# Nucleo.net
KiCad netlist of a schematic drawn in Altium Designer
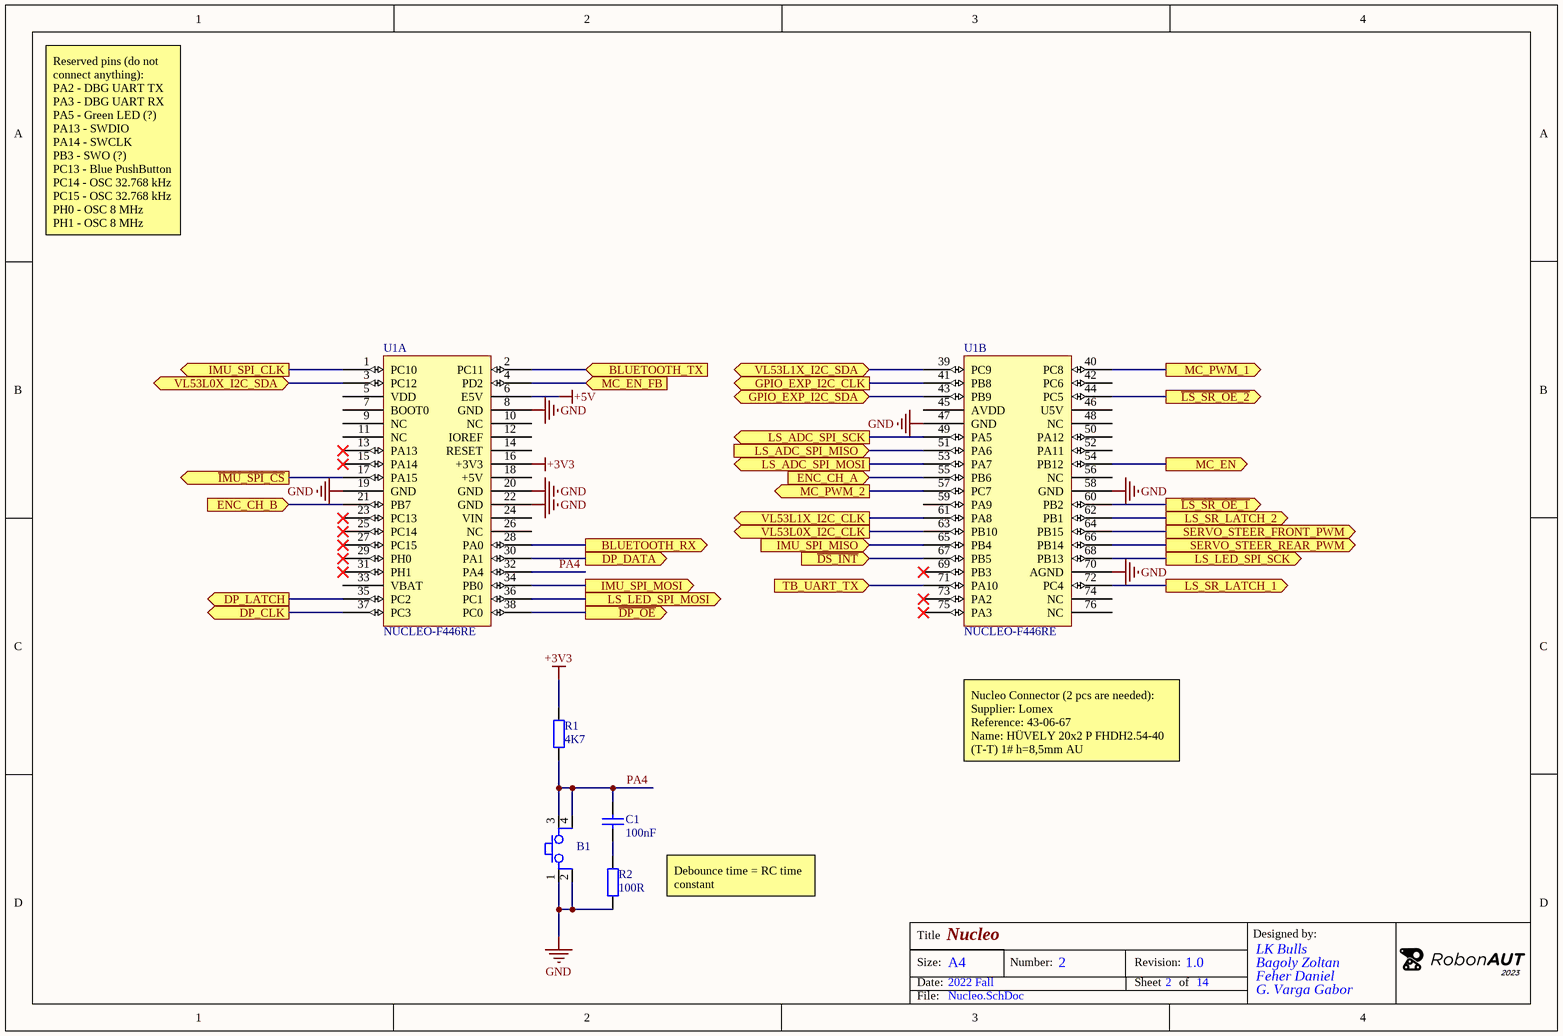
[diagram p0: Nucleo.SchDoc]

(export (version "E")
  (design (tool "Eeschema 10.0.6"))
  (components
    (comp (ref "B1")
      (value "Button")
      (footprint "FP_BTN_SMD")
      (description "Push button")
      (libsource (lib "LKBulls2023") (part "Button 4P"))
    )
    (comp (ref "C1")
      (value "100nF")
      (footprint "FP_0805_CAP_085")
      (description "Capacitor")
      (fields (field (name "TOLERANCE") "10%") (field (name "VOLTAGE") "50V"))
      (libsource (lib "LKBulls2023") (part "CAP"))
    )
    (comp (ref "R1")
      (value "4K7")
      (footprint "FP_0805_RES")
      (description "Resistor")
      (fields (field (name "TOLERANCE") "5%") (field (name "POWER") "0.125W"))
      (libsource (lib "") (part "RES_1"))
    )
    (comp (ref "R2")
      (value "100R")
      (footprint "FP_0805_RES")
      (description "Resistor")
      (fields (field (name "TOLERANCE") "5%") (field (name "POWER") "0.125W"))
      (libsource (lib "LKBulls2023") (part "RES"))
    )
    (comp (ref "U1")
      (value "NUCLEO-F446RE")
      (footprint "FP_NUCLEO-64")
      (libsource (lib "LKBulls2023") (part "NUCLEO-F446RE"))
    )
  )
  (nets
    (net (code "1") (name "+3V3") (class "Default")
      (node (ref "R1") (pin "2") (pinfunction "2_2") (pintype "passive"))
      (node (ref "U1") (pin "16") (pinfunction "+3V3_16") (pintype "power_in"))
    )
    (net (code "2") (name "+5V") (class "Default")
      (node (ref "U1") (pin "6") (pinfunction "E5V_6") (pintype "power_in"))
    )
    (net (code "3") (name "/BLUETOOTH_RX") (class "Default")
      (node (ref "U1") (pin "28") (pinfunction "PA0_28") (pintype "bidirectional"))
    )
    (net (code "4") (name "/BLUETOOTH_TX") (class "Default")
      (node (ref "U1") (pin "2") (pinfunction "PC11_2") (pintype "bidirectional"))
    )
    (net (code "5") (name "/DP_CLK") (class "Default")
      (node (ref "U1") (pin "37") (pinfunction "PC3_37") (pintype "bidirectional"))
    )
    (net (code "6") (name "/DP_DATA") (class "Default")
      (node (ref "U1") (pin "30") (pinfunction "PA1_30") (pintype "bidirectional"))
    )
    (net (code "7") (name "/DP_LATCH") (class "Default")
      (node (ref "U1") (pin "35") (pinfunction "PC2_35") (pintype "bidirectional"))
    )
    (net (code "8") (name "/ENC_CH_A") (class "Default")
      (node (ref "U1") (pin "55") (pinfunction "PB6_55") (pintype "bidirectional"))
    )
    (net (code "9") (name "/ENC_CH_B") (class "Default")
      (node (ref "U1") (pin "21") (pinfunction "PB7_21") (pintype "bidirectional"))
    )
    (net (code "10") (name "/GPIO_EXP_I2C_CLK") (class "Default")
      (node (ref "U1") (pin "41") (pinfunction "PB8_41") (pintype "bidirectional"))
    )
    (net (code "11") (name "/GPIO_EXP_I2C_SDA") (class "Default")
      (node (ref "U1") (pin "43") (pinfunction "PB9_43") (pintype "bidirectional"))
    )
    (net (code "12") (name "/IMU_SPI_CLK") (class "Default")
      (node (ref "U1") (pin "1") (pinfunction "PC10_1") (pintype "bidirectional"))
    )
    (net (code "13") (name "/IMU_SPI_MISO") (class "Default")
      (node (ref "U1") (pin "65") (pinfunction "PB4_65") (pintype "bidirectional"))
    )
    (net (code "14") (name "/IMU_SPI_MOSI") (class "Default")
      (node (ref "U1") (pin "34") (pinfunction "PB0_34") (pintype "bidirectional"))
    )
    (net (code "15") (name "/LS_ADC_SPI_MISO") (class "Default")
      (node (ref "U1") (pin "51") (pinfunction "PA6_51") (pintype "bidirectional"))
    )
    (net (code "16") (name "/LS_ADC_SPI_MOSI") (class "Default")
      (node (ref "U1") (pin "53") (pinfunction "PA7_53") (pintype "bidirectional"))
    )
    (net (code "17") (name "/LS_ADC_SPI_SCK") (class "Default")
      (node (ref "U1") (pin "49") (pinfunction "PA5_49") (pintype "bidirectional"))
    )
    (net (code "18") (name "/LS_LED_SPI_MOSI") (class "Default")
      (node (ref "U1") (pin "36") (pinfunction "PC1_36") (pintype "bidirectional"))
    )
    (net (code "19") (name "/LS_LED_SPI_SCK") (class "Default")
      (node (ref "U1") (pin "68") (pinfunction "PB13_68") (pintype "bidirectional"))
    )
    (net (code "20") (name "/LS_SR_LATCH_1") (class "Default")
      (node (ref "U1") (pin "72") (pinfunction "PC4_72") (pintype "bidirectional"))
    )
    (net (code "21") (name "/LS_SR_LATCH_2") (class "Default")
      (node (ref "U1") (pin "62") (pinfunction "PB1_62") (pintype "bidirectional"))
    )
    (net (code "22") (name "/MC_EN") (class "Default")
      (node (ref "U1") (pin "54") (pinfunction "PB12_54") (pintype "bidirectional"))
    )
    (net (code "23") (name "/MC_EN_FB") (class "Default")
      (node (ref "U1") (pin "4") (pinfunction "PD2_4") (pintype "bidirectional"))
    )
    (net (code "24") (name "/MC_PWM_1") (class "Default")
      (node (ref "U1") (pin "40") (pinfunction "PC8_40") (pintype "bidirectional"))
    )
    (net (code "25") (name "/MC_PWM_2") (class "Default")
      (node (ref "U1") (pin "57") (pinfunction "PC7_57") (pintype "bidirectional"))
    )
    (net (code "26") (name "/PA4") (class "Default")
      (node (ref "B1") (pin "3") (pinfunction "3_3") (pintype "passive"))
      (node (ref "B1") (pin "4") (pinfunction "4_4") (pintype "passive"))
      (node (ref "C1") (pin "2") (pinfunction "2_2") (pintype "passive"))
      (node (ref "R1") (pin "1") (pinfunction "1_1") (pintype "passive"))
      (node (ref "U1") (pin "32") (pinfunction "PA4_32") (pintype "bidirectional"))
    )
    (net (code "27") (name "/SERVO_STEER_FRONT_PWM") (class "Default")
      (node (ref "U1") (pin "64") (pinfunction "PB15_64") (pintype "bidirectional"))
    )
    (net (code "28") (name "/SERVO_STEER_REAR_PWM") (class "Default")
      (node (ref "U1") (pin "66") (pinfunction "PB14_66") (pintype "bidirectional"))
    )
    (net (code "29") (name "/TB_UART_TX") (class "Default")
      (node (ref "U1") (pin "71") (pinfunction "PA10_71") (pintype "bidirectional"))
    )
    (net (code "30") (name "/VL53L0X_I2C_CLK") (class "Default")
      (node (ref "U1") (pin "63") (pinfunction "PB10_63") (pintype "bidirectional"))
    )
    (net (code "31") (name "/VL53L0X_I2C_SDA") (class "Default")
      (node (ref "U1") (pin "3") (pinfunction "PC12_3") (pintype "bidirectional"))
    )
    (net (code "32") (name "/VL53L1X_I2C_CLK") (class "Default")
      (node (ref "U1") (pin "61") (pinfunction "PA8_61") (pintype "bidirectional"))
    )
    (net (code "33") (name "/VL53L1X_I2C_SDA") (class "Default")
      (node (ref "U1") (pin "39") (pinfunction "PC9_39") (pintype "bidirectional"))
    )
    (net (code "34") (name "/~{DP_OE}") (class "Default")
      (node (ref "U1") (pin "38") (pinfunction "PC0_38") (pintype "bidirectional"))
    )
    (net (code "35") (name "/~{DS_INT}") (class "Default")
      (node (ref "U1") (pin "67") (pinfunction "PB5_67") (pintype "bidirectional"))
    )
    (net (code "36") (name "/~{IMU_SPI_CS}") (class "Default")
      (node (ref "U1") (pin "17") (pinfunction "PA15_17") (pintype "bidirectional"))
    )
    (net (code "37") (name "/~{LS_SR_OE_1}") (class "Default")
      (node (ref "U1") (pin "60") (pinfunction "PB2_60") (pintype "bidirectional"))
    )
    (net (code "38") (name "/~{LS_SR_OE_2}") (class "Default")
      (node (ref "U1") (pin "44") (pinfunction "PC5_44") (pintype "bidirectional"))
    )
    (net (code "39") (name "GND") (class "Default")
      (node (ref "B1") (pin "1") (pinfunction "1_1") (pintype "passive"))
      (node (ref "B1") (pin "2") (pinfunction "2_2") (pintype "passive"))
      (node (ref "R2") (pin "2") (pinfunction "2_2") (pintype "passive"))
      (node (ref "U1") (pin "19") (pinfunction "GND_19") (pintype "passive"))
      (node (ref "U1") (pin "20") (pinfunction "GND_20") (pintype "passive"))
      (node (ref "U1") (pin "22") (pinfunction "GND_22") (pintype "passive"))
      (node (ref "U1") (pin "47") (pinfunction "GND_47") (pintype "passive"))
      (node (ref "U1") (pin "58") (pinfunction "GND_58") (pintype "passive"))
      (node (ref "U1") (pin "70") (pinfunction "AGND_70") (pintype "passive"))
      (node (ref "U1") (pin "8") (pinfunction "GND_8") (pintype "passive"))
    )
    (net (code "40") (name "Net-(C1-Pad1)") (class "Default")
      (node (ref "C1") (pin "1") (pinfunction "1_1") (pintype "passive"))
      (node (ref "R2") (pin "1") (pinfunction "1_1") (pintype "passive"))
    )
    (net (code "41") (name "unconnected-(U1A-+5V-Pad18)") (class "Default")
      (node (ref "U1") (pin "18") (pinfunction "+5V_18") (pintype "power_in"))
    )
    (net (code "42") (name "unconnected-(U1A-BOOT0-Pad7)") (class "Default")
      (node (ref "U1") (pin "7") (pinfunction "BOOT0_7") (pintype "passive"))
    )
    (net (code "43") (name "unconnected-(U1A-IOREF-Pad12)") (class "Default")
      (node (ref "U1") (pin "12") (pinfunction "IOREF_12") (pintype "passive"))
    )
    (net (code "44") (name "unconnected-(U1A-NC-Pad9)") (class "Default")
      (node (ref "U1") (pin "9") (pinfunction "NC_9") (pintype "passive"))
    )
    (net (code "45") (name "unconnected-(U1A-NC-Pad10)") (class "Default")
      (node (ref "U1") (pin "10") (pinfunction "NC_10") (pintype "passive"))
    )
    (net (code "46") (name "unconnected-(U1A-NC-Pad11)") (class "Default")
      (node (ref "U1") (pin "11") (pinfunction "NC_11") (pintype "passive"))
    )
    (net (code "47") (name "unconnected-(U1A-NC-Pad26)") (class "Default")
      (node (ref "U1") (pin "26") (pinfunction "NC_26") (pintype "passive"))
    )
    (net (code "48") (name "unconnected-(U1A-PA13-Pad13)") (class "Default")
      (node (ref "U1") (pin "13") (pinfunction "PA13_13") (pintype "bidirectional+no_connect"))
    )
    (net (code "49") (name "unconnected-(U1A-PA14-Pad15)") (class "Default")
      (node (ref "U1") (pin "15") (pinfunction "PA14_15") (pintype "bidirectional+no_connect"))
    )
    (net (code "50") (name "unconnected-(U1A-PC13-Pad23)") (class "Default")
      (node (ref "U1") (pin "23") (pinfunction "PC13_23") (pintype "bidirectional+no_connect"))
    )
    (net (code "51") (name "unconnected-(U1A-PC14-Pad25)") (class "Default")
      (node (ref "U1") (pin "25") (pinfunction "PC14_25") (pintype "bidirectional+no_connect"))
    )
    (net (code "52") (name "unconnected-(U1A-PC15-Pad27)") (class "Default")
      (node (ref "U1") (pin "27") (pinfunction "PC15_27") (pintype "bidirectional+no_connect"))
    )
    (net (code "53") (name "unconnected-(U1A-PH0-Pad29)") (class "Default")
      (node (ref "U1") (pin "29") (pinfunction "PH0_29") (pintype "bidirectional+no_connect"))
    )
    (net (code "54") (name "unconnected-(U1A-PH1-Pad31)") (class "Default")
      (node (ref "U1") (pin "31") (pinfunction "PH1_31") (pintype "bidirectional+no_connect"))
    )
    (net (code "55") (name "unconnected-(U1A-RESET-Pad14)") (class "Default")
      (node (ref "U1") (pin "14") (pinfunction "RESET_14") (pintype "passive"))
    )
    (net (code "56") (name "unconnected-(U1A-VBAT-Pad33)") (class "Default")
      (node (ref "U1") (pin "33") (pinfunction "VBAT_33") (pintype "power_in"))
    )
    (net (code "57") (name "unconnected-(U1A-VDD-Pad5)") (class "Default")
      (node (ref "U1") (pin "5") (pinfunction "VDD_5") (pintype "power_in"))
    )
    (net (code "58") (name "unconnected-(U1A-VIN-Pad24)") (class "Default")
      (node (ref "U1") (pin "24") (pinfunction "VIN_24") (pintype "power_in"))
    )
    (net (code "59") (name "unconnected-(U1B-AVDD-Pad45)") (class "Default")
      (node (ref "U1") (pin "45") (pinfunction "AVDD_45") (pintype "power_in"))
    )
    (net (code "60") (name "unconnected-(U1B-NC-Pad48)") (class "Default")
      (node (ref "U1") (pin "48") (pinfunction "NC_48") (pintype "passive"))
    )
    (net (code "61") (name "unconnected-(U1B-NC-Pad56)") (class "Default")
      (node (ref "U1") (pin "56") (pinfunction "NC_56") (pintype "passive"))
    )
    (net (code "62") (name "unconnected-(U1B-NC-Pad74)") (class "Default")
      (node (ref "U1") (pin "74") (pinfunction "NC_74") (pintype "passive"))
    )
    (net (code "63") (name "unconnected-(U1B-NC-Pad76)") (class "Default")
      (node (ref "U1") (pin "76") (pinfunction "NC_76") (pintype "passive"))
    )
    (net (code "64") (name "unconnected-(U1B-PA2-Pad73)") (class "Default")
      (node (ref "U1") (pin "73") (pinfunction "PA2_73") (pintype "bidirectional+no_connect"))
    )
    (net (code "65") (name "unconnected-(U1B-PA3-Pad75)") (class "Default")
      (node (ref "U1") (pin "75") (pinfunction "PA3_75") (pintype "bidirectional+no_connect"))
    )
    (net (code "66") (name "unconnected-(U1B-PA9-Pad59)") (class "Default")
      (node (ref "U1") (pin "59") (pinfunction "PA9_59") (pintype "bidirectional"))
    )
    (net (code "67") (name "unconnected-(U1B-PA11-Pad52)") (class "Default")
      (node (ref "U1") (pin "52") (pinfunction "PA11_52") (pintype "bidirectional"))
    )
    (net (code "68") (name "unconnected-(U1B-PA12-Pad50)") (class "Default")
      (node (ref "U1") (pin "50") (pinfunction "PA12_50") (pintype "bidirectional"))
    )
    (net (code "69") (name "unconnected-(U1B-PB3-Pad69)") (class "Default")
      (node (ref "U1") (pin "69") (pinfunction "PB3_69") (pintype "bidirectional+no_connect"))
    )
    (net (code "70") (name "unconnected-(U1B-PC6-Pad42)") (class "Default")
      (node (ref "U1") (pin "42") (pinfunction "PC6_42") (pintype "bidirectional"))
    )
    (net (code "71") (name "unconnected-(U1B-U5V-Pad46)") (class "Default")
      (node (ref "U1") (pin "46") (pinfunction "U5V_46") (pintype "power_in"))
    )
  )
)
